# TDA2003.net
KiCad netlist of a schematic drawn in EAGLE
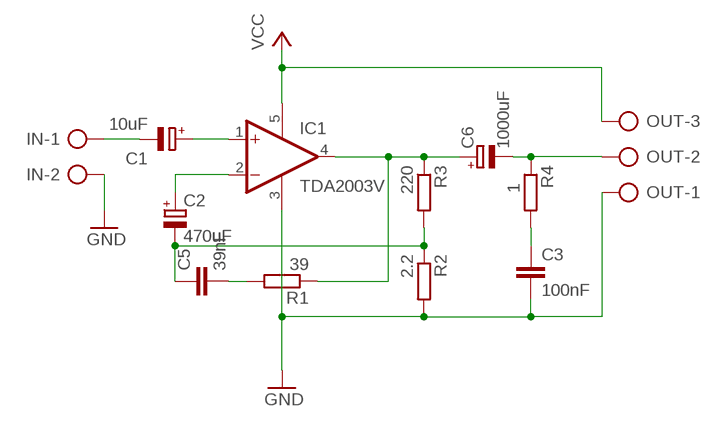
[diagram p0: schematic, sheet 1]

(export (version "E")
  (design (tool "Eeschema 10.0.6"))
  (components
    (comp (ref "C1")
      (value "10uF")
      (footprint "eagle-import:E2,5-6")
      (libsource (lib "eagle-import") (part "CPOL-EUE2.5-6"))
    )
    (comp (ref "C2")
      (value "470uF")
      (footprint "eagle-import:E5-10,5")
      (libsource (lib "eagle-import") (part "CPOL-EUE5-10.5"))
    )
    (comp (ref "C3")
      (value "100nF")
      (footprint "eagle-import:C025-025X050")
      (libsource (lib "eagle-import") (part "C-EU025-025X050"))
    )
    (comp (ref "C5")
      (value "39nF")
      (footprint "eagle-import:C025-025X050")
      (libsource (lib "eagle-import") (part "C-EU025-025X050"))
    )
    (comp (ref "C6")
      (value "1000uF")
      (footprint "eagle-import:E5-13")
      (libsource (lib "eagle-import") (part "CPOL-EUE5-13"))
    )
    (comp (ref "IC1")
      (value "TDA2003V")
      (footprint "eagle-import:CB360")
      (libsource (lib "eagle-import") (part "TDA2003V"))
    )
    (comp (ref "IN")
      (value "AK500/2-H")
      (footprint "eagle-import:AK500_2-H")
      (libsource (lib "eagle-import") (part "AK500/2-H"))
    )
    (comp (ref "OUT")
      (value "AK500/3-H")
      (footprint "eagle-import:AK500_3-H")
      (libsource (lib "eagle-import") (part "AK500/3-H"))
    )
    (comp (ref "R1")
      (value "39")
      (footprint "eagle-import:0207_10")
      (libsource (lib "eagle-import") (part "R-EU_0207/10"))
    )
    (comp (ref "R2")
      (value "2.2")
      (footprint "eagle-import:0207_10")
      (libsource (lib "eagle-import") (part "R-EU_0207/10"))
    )
    (comp (ref "R3")
      (value "220")
      (footprint "eagle-import:0207_10")
      (libsource (lib "eagle-import") (part "R-EU_0207/10"))
    )
    (comp (ref "R4")
      (value "1")
      (footprint "eagle-import:0207_10")
      (libsource (lib "eagle-import") (part "R-EU_0207/10"))
    )
  )
  (nets
    (net (code "1") (name "GND") (class "Default")
      (node (ref "C3") (pin "2") (pinfunction "2_2") (pintype "passive"))
      (node (ref "IC1") (pin "3") (pinfunction "GND_3") (pintype "power_in"))
      (node (ref "IN") (pin "2") (pinfunction "KL_2") (pintype "passive"))
      (node (ref "OUT") (pin "1") (pinfunction "KL_1") (pintype "passive"))
      (node (ref "R2") (pin "2") (pinfunction "2_2") (pintype "passive"))
    )
    (net (code "2") (name "Net-(C2-Pad-)") (class "Default")
      (node (ref "C2") (pin "-") (pinfunction "-_-") (pintype "passive"))
      (node (ref "C5") (pin "1") (pinfunction "1_1") (pintype "passive"))
      (node (ref "R2") (pin "1") (pinfunction "1_1") (pintype "passive"))
      (node (ref "R3") (pin "2") (pinfunction "2_2") (pintype "passive"))
    )
    (net (code "3") (name "Net-(C3-Pad1)") (class "Default")
      (node (ref "C3") (pin "1") (pinfunction "1_1") (pintype "passive"))
      (node (ref "R4") (pin "2") (pinfunction "2_2") (pintype "passive"))
    )
    (net (code "4") (name "Net-(C5-Pad2)") (class "Default")
      (node (ref "C5") (pin "2") (pinfunction "2_2") (pintype "passive"))
      (node (ref "R1") (pin "2") (pinfunction "2_2") (pintype "passive"))
    )
    (net (code "5") (name "Net-(IC1-+IN)") (class "Default")
      (node (ref "C1") (pin "+") (pinfunction "+_+") (pintype "passive"))
      (node (ref "IC1") (pin "1") (pinfunction "+IN_1") (pintype "input"))
    )
    (net (code "6") (name "Net-(IC1--IN)") (class "Default")
      (node (ref "C2") (pin "+") (pinfunction "+_+") (pintype "passive"))
      (node (ref "IC1") (pin "2") (pinfunction "-IN_2") (pintype "input"))
    )
    (net (code "7") (name "Net-(IC1-OUT)") (class "Default")
      (node (ref "C6") (pin "+") (pinfunction "+_+") (pintype "passive"))
      (node (ref "IC1") (pin "4") (pinfunction "OUT_4") (pintype "output"))
      (node (ref "R1") (pin "1") (pinfunction "1_1") (pintype "passive"))
      (node (ref "R3") (pin "1") (pinfunction "1_1") (pintype "passive"))
    )
    (net (code "8") (name "Net-(INA-KL)") (class "Default")
      (node (ref "C1") (pin "-") (pinfunction "-_-") (pintype "passive"))
      (node (ref "IN") (pin "1") (pinfunction "KL_1") (pintype "passive"))
    )
    (net (code "9") (name "Net-(OUTB-KL)") (class "Default")
      (node (ref "C6") (pin "-") (pinfunction "-_-") (pintype "passive"))
      (node (ref "OUT") (pin "2") (pinfunction "KL_2") (pintype "passive"))
      (node (ref "R4") (pin "1") (pinfunction "1_1") (pintype "passive"))
    )
    (net (code "10") (name "VCC") (class "Default")
      (node (ref "IC1") (pin "5") (pinfunction "V+_5") (pintype "power_in"))
      (node (ref "OUT") (pin "3") (pinfunction "KL_3") (pintype "passive"))
    )
  )
)
